# headers.net
KiCad netlist of a schematic drawn in Altium Designer
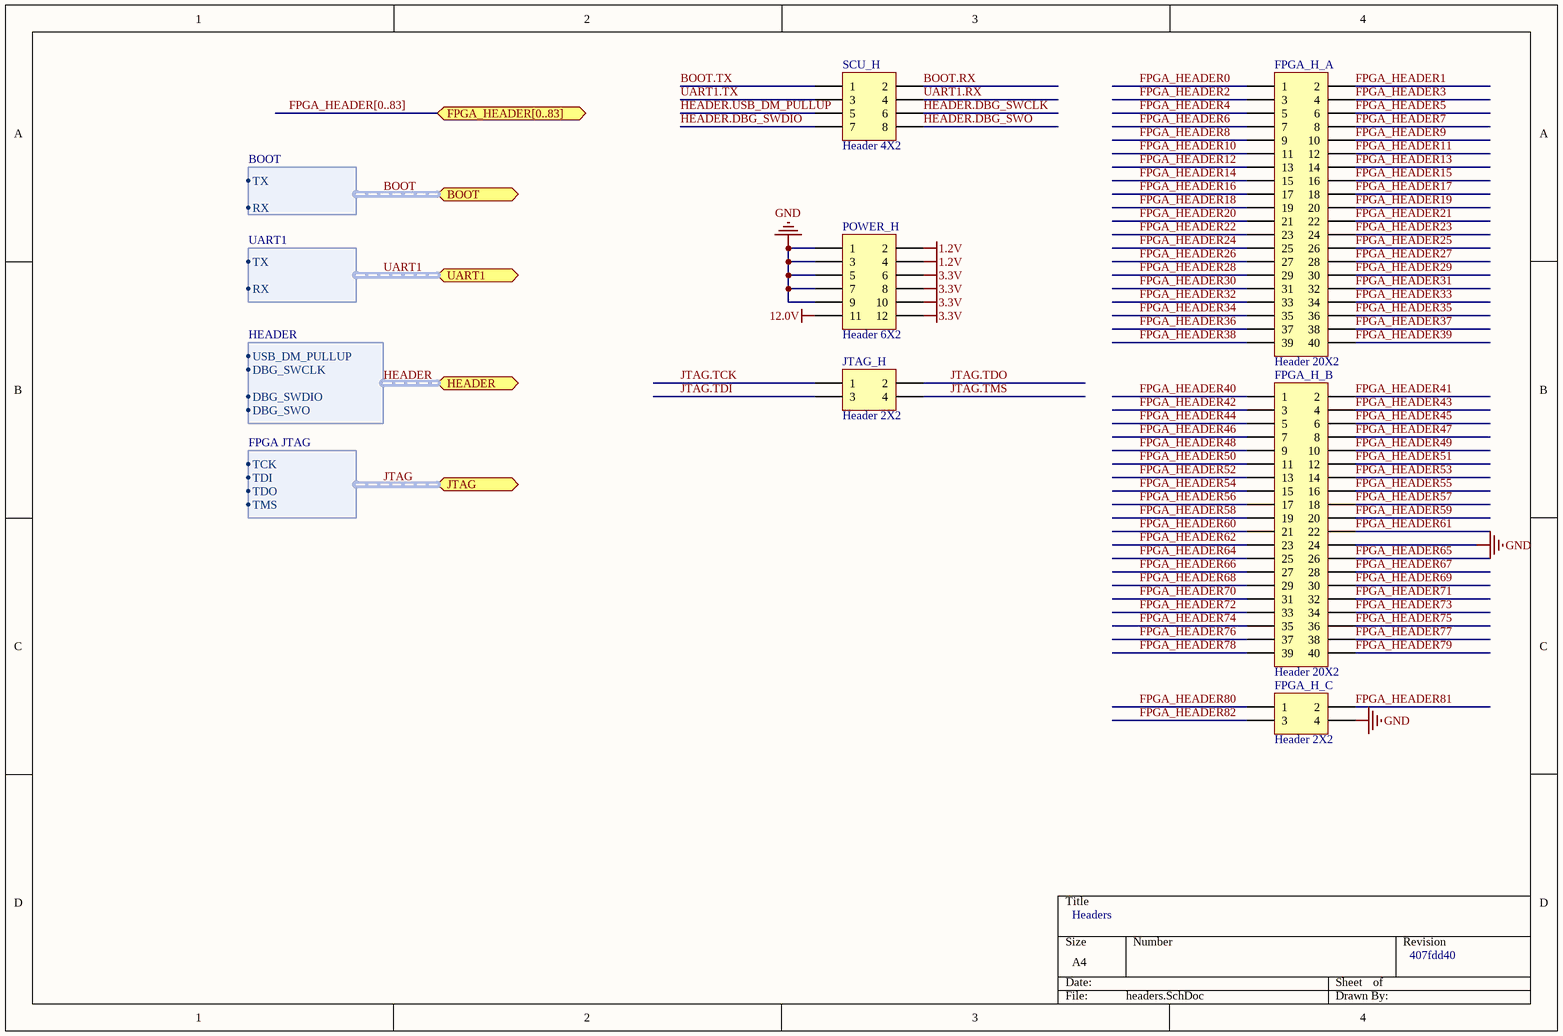
[diagram p0: headers.SchDoc]

(export (version "E")
  (design (tool "Eeschema 10.0.6"))
  (components
    (comp (ref "FPGA_H_A")
      (value "Header 20X2")
      (footprint "HDR2X20")
      (description "Header, 20-Pin, Dual row")
      (fields (field (name "PUBLISHER") "Altium Limited"))
      (libsource (lib "Miscellaneous Connectors") (part "Header 20X2"))
    )
    (comp (ref "FPGA_H_B")
      (value "Header 20X2")
      (footprint "HDR2X20")
      (description "Header, 20-Pin, Dual row")
      (fields (field (name "PUBLISHER") "Altium Limited"))
      (libsource (lib "Miscellaneous Connectors") (part "Header 20X2"))
    )
    (comp (ref "FPGA_H_C")
      (value "Header 2X2")
      (footprint "HDR2X2")
      (description "Header, 2-Pin, Dual row")
      (fields (field (name "PUBLISHER") "Altium Limited"))
      (libsource (lib "Miscellaneous Connectors") (part "Header 2X2"))
    )
    (comp (ref "JTAG_H")
      (value "Header 2X2")
      (footprint "HDR2X2")
      (description "Header, 2-Pin, Dual row")
      (fields (field (name "PUBLISHER") "Altium Limited"))
      (libsource (lib "Miscellaneous Connectors") (part "Header 2X2"))
    )
    (comp (ref "POWER_H")
      (value "Header 6X2")
      (footprint "HDR2X6")
      (description "Header, 6-Pin, Dual row")
      (fields (field (name "PUBLISHER") "Altium Limited"))
      (libsource (lib "Miscellaneous Connectors") (part "Header 6X2"))
    )
    (comp (ref "SCU_H")
      (value "Header 4X2")
      (footprint "HDR2X4")
      (description "Header, 4-Pin, Dual row")
      (fields (field (name "PUBLISHER") "Altium Limited"))
      (libsource (lib "Miscellaneous Connectors") (part "Header 4X2"))
    )
  )
  (nets
    (net (code "8") (name "/BOOT.RX") (class "Default")
      (node (ref "SCU_H") (pin "2") (pinfunction "2_2") (pintype "passive"))
    )
    (net (code "9") (name "/BOOT.TX") (class "Default")
      (node (ref "SCU_H") (pin "1") (pinfunction "1_1") (pintype "passive"))
    )
    (net (code "11") (name "/FPGA_HEADER0") (class "Default")
      (node (ref "FPGA_H_A") (pin "1") (pinfunction "1_1") (pintype "passive"))
    )
    (net (code "12") (name "/FPGA_HEADER1") (class "Default")
      (node (ref "FPGA_H_A") (pin "2") (pinfunction "2_2") (pintype "passive"))
    )
    (net (code "13") (name "/FPGA_HEADER2") (class "Default")
      (node (ref "FPGA_H_A") (pin "3") (pinfunction "3_3") (pintype "passive"))
    )
    (net (code "14") (name "/FPGA_HEADER3") (class "Default")
      (node (ref "FPGA_H_A") (pin "4") (pinfunction "4_4") (pintype "passive"))
    )
    (net (code "15") (name "/FPGA_HEADER4") (class "Default")
      (node (ref "FPGA_H_A") (pin "5") (pinfunction "5_5") (pintype "passive"))
    )
    (net (code "16") (name "/FPGA_HEADER5") (class "Default")
      (node (ref "FPGA_H_A") (pin "6") (pinfunction "6_6") (pintype "passive"))
    )
    (net (code "17") (name "/FPGA_HEADER6") (class "Default")
      (node (ref "FPGA_H_A") (pin "7") (pinfunction "7_7") (pintype "passive"))
    )
    (net (code "18") (name "/FPGA_HEADER7") (class "Default")
      (node (ref "FPGA_H_A") (pin "8") (pinfunction "8_8") (pintype "passive"))
    )
    (net (code "19") (name "/FPGA_HEADER8") (class "Default")
      (node (ref "FPGA_H_A") (pin "9") (pinfunction "9_9") (pintype "passive"))
    )
    (net (code "20") (name "/FPGA_HEADER9") (class "Default")
      (node (ref "FPGA_H_A") (pin "10") (pinfunction "10_10") (pintype "passive"))
    )
    (net (code "21") (name "/FPGA_HEADER10") (class "Default")
      (node (ref "FPGA_H_A") (pin "11") (pinfunction "11_11") (pintype "passive"))
    )
    (net (code "22") (name "/FPGA_HEADER11") (class "Default")
      (node (ref "FPGA_H_A") (pin "12") (pinfunction "12_12") (pintype "passive"))
    )
    (net (code "23") (name "/FPGA_HEADER12") (class "Default")
      (node (ref "FPGA_H_A") (pin "13") (pinfunction "13_13") (pintype "passive"))
    )
    (net (code "24") (name "/FPGA_HEADER13") (class "Default")
      (node (ref "FPGA_H_A") (pin "14") (pinfunction "14_14") (pintype "passive"))
    )
    (net (code "25") (name "/FPGA_HEADER14") (class "Default")
      (node (ref "FPGA_H_A") (pin "15") (pinfunction "15_15") (pintype "passive"))
    )
    (net (code "26") (name "/FPGA_HEADER15") (class "Default")
      (node (ref "FPGA_H_A") (pin "16") (pinfunction "16_16") (pintype "passive"))
    )
    (net (code "27") (name "/FPGA_HEADER16") (class "Default")
      (node (ref "FPGA_H_A") (pin "17") (pinfunction "17_17") (pintype "passive"))
    )
    (net (code "28") (name "/FPGA_HEADER17") (class "Default")
      (node (ref "FPGA_H_A") (pin "18") (pinfunction "18_18") (pintype "passive"))
    )
    (net (code "29") (name "/FPGA_HEADER18") (class "Default")
      (node (ref "FPGA_H_A") (pin "19") (pinfunction "19_19") (pintype "passive"))
    )
    (net (code "30") (name "/FPGA_HEADER19") (class "Default")
      (node (ref "FPGA_H_A") (pin "20") (pinfunction "20_20") (pintype "passive"))
    )
    (net (code "31") (name "/FPGA_HEADER20") (class "Default")
      (node (ref "FPGA_H_A") (pin "21") (pinfunction "21_21") (pintype "passive"))
    )
    (net (code "32") (name "/FPGA_HEADER21") (class "Default")
      (node (ref "FPGA_H_A") (pin "22") (pinfunction "22_22") (pintype "passive"))
    )
    (net (code "33") (name "/FPGA_HEADER22") (class "Default")
      (node (ref "FPGA_H_A") (pin "23") (pinfunction "23_23") (pintype "passive"))
    )
    (net (code "34") (name "/FPGA_HEADER23") (class "Default")
      (node (ref "FPGA_H_A") (pin "24") (pinfunction "24_24") (pintype "passive"))
    )
    (net (code "35") (name "/FPGA_HEADER24") (class "Default")
      (node (ref "FPGA_H_A") (pin "25") (pinfunction "25_25") (pintype "passive"))
    )
    (net (code "36") (name "/FPGA_HEADER25") (class "Default")
      (node (ref "FPGA_H_A") (pin "26") (pinfunction "26_26") (pintype "passive"))
    )
    (net (code "37") (name "/FPGA_HEADER26") (class "Default")
      (node (ref "FPGA_H_A") (pin "27") (pinfunction "27_27") (pintype "passive"))
    )
    (net (code "38") (name "/FPGA_HEADER27") (class "Default")
      (node (ref "FPGA_H_A") (pin "28") (pinfunction "28_28") (pintype "passive"))
    )
    (net (code "39") (name "/FPGA_HEADER28") (class "Default")
      (node (ref "FPGA_H_A") (pin "29") (pinfunction "29_29") (pintype "passive"))
    )
    (net (code "40") (name "/FPGA_HEADER29") (class "Default")
      (node (ref "FPGA_H_A") (pin "30") (pinfunction "30_30") (pintype "passive"))
    )
    (net (code "41") (name "/FPGA_HEADER30") (class "Default")
      (node (ref "FPGA_H_A") (pin "31") (pinfunction "31_31") (pintype "passive"))
    )
    (net (code "42") (name "/FPGA_HEADER31") (class "Default")
      (node (ref "FPGA_H_A") (pin "32") (pinfunction "32_32") (pintype "passive"))
    )
    (net (code "43") (name "/FPGA_HEADER32") (class "Default")
      (node (ref "FPGA_H_A") (pin "33") (pinfunction "33_33") (pintype "passive"))
    )
    (net (code "44") (name "/FPGA_HEADER33") (class "Default")
      (node (ref "FPGA_H_A") (pin "34") (pinfunction "34_34") (pintype "passive"))
    )
    (net (code "45") (name "/FPGA_HEADER34") (class "Default")
      (node (ref "FPGA_H_A") (pin "35") (pinfunction "35_35") (pintype "passive"))
    )
    (net (code "46") (name "/FPGA_HEADER35") (class "Default")
      (node (ref "FPGA_H_A") (pin "36") (pinfunction "36_36") (pintype "passive"))
    )
    (net (code "47") (name "/FPGA_HEADER36") (class "Default")
      (node (ref "FPGA_H_A") (pin "37") (pinfunction "37_37") (pintype "passive"))
    )
    (net (code "48") (name "/FPGA_HEADER37") (class "Default")
      (node (ref "FPGA_H_A") (pin "38") (pinfunction "38_38") (pintype "passive"))
    )
    (net (code "49") (name "/FPGA_HEADER38") (class "Default")
      (node (ref "FPGA_H_A") (pin "39") (pinfunction "39_39") (pintype "passive"))
    )
    (net (code "50") (name "/FPGA_HEADER39") (class "Default")
      (node (ref "FPGA_H_A") (pin "40") (pinfunction "40_40") (pintype "passive"))
    )
    (net (code "51") (name "/FPGA_HEADER40") (class "Default")
      (node (ref "FPGA_H_B") (pin "1") (pinfunction "1_1") (pintype "passive"))
    )
    (net (code "52") (name "/FPGA_HEADER41") (class "Default")
      (node (ref "FPGA_H_B") (pin "2") (pinfunction "2_2") (pintype "passive"))
    )
    (net (code "53") (name "/FPGA_HEADER42") (class "Default")
      (node (ref "FPGA_H_B") (pin "3") (pinfunction "3_3") (pintype "passive"))
    )
    (net (code "54") (name "/FPGA_HEADER43") (class "Default")
      (node (ref "FPGA_H_B") (pin "4") (pinfunction "4_4") (pintype "passive"))
    )
    (net (code "55") (name "/FPGA_HEADER44") (class "Default")
      (node (ref "FPGA_H_B") (pin "5") (pinfunction "5_5") (pintype "passive"))
    )
    (net (code "56") (name "/FPGA_HEADER45") (class "Default")
      (node (ref "FPGA_H_B") (pin "6") (pinfunction "6_6") (pintype "passive"))
    )
    (net (code "57") (name "/FPGA_HEADER46") (class "Default")
      (node (ref "FPGA_H_B") (pin "7") (pinfunction "7_7") (pintype "passive"))
    )
    (net (code "58") (name "/FPGA_HEADER47") (class "Default")
      (node (ref "FPGA_H_B") (pin "8") (pinfunction "8_8") (pintype "passive"))
    )
    (net (code "59") (name "/FPGA_HEADER48") (class "Default")
      (node (ref "FPGA_H_B") (pin "9") (pinfunction "9_9") (pintype "passive"))
    )
    (net (code "60") (name "/FPGA_HEADER49") (class "Default")
      (node (ref "FPGA_H_B") (pin "10") (pinfunction "10_10") (pintype "passive"))
    )
    (net (code "61") (name "/FPGA_HEADER50") (class "Default")
      (node (ref "FPGA_H_B") (pin "11") (pinfunction "11_11") (pintype "passive"))
    )
    (net (code "62") (name "/FPGA_HEADER51") (class "Default")
      (node (ref "FPGA_H_B") (pin "12") (pinfunction "12_12") (pintype "passive"))
    )
    (net (code "63") (name "/FPGA_HEADER52") (class "Default")
      (node (ref "FPGA_H_B") (pin "13") (pinfunction "13_13") (pintype "passive"))
    )
    (net (code "64") (name "/FPGA_HEADER53") (class "Default")
      (node (ref "FPGA_H_B") (pin "14") (pinfunction "14_14") (pintype "passive"))
    )
    (net (code "65") (name "/FPGA_HEADER54") (class "Default")
      (node (ref "FPGA_H_B") (pin "15") (pinfunction "15_15") (pintype "passive"))
    )
    (net (code "66") (name "/FPGA_HEADER55") (class "Default")
      (node (ref "FPGA_H_B") (pin "16") (pinfunction "16_16") (pintype "passive"))
    )
    (net (code "67") (name "/FPGA_HEADER56") (class "Default")
      (node (ref "FPGA_H_B") (pin "17") (pinfunction "17_17") (pintype "passive"))
    )
    (net (code "68") (name "/FPGA_HEADER57") (class "Default")
      (node (ref "FPGA_H_B") (pin "18") (pinfunction "18_18") (pintype "passive"))
    )
    (net (code "69") (name "/FPGA_HEADER58") (class "Default")
      (node (ref "FPGA_H_B") (pin "19") (pinfunction "19_19") (pintype "passive"))
    )
    (net (code "70") (name "/FPGA_HEADER59") (class "Default")
      (node (ref "FPGA_H_B") (pin "20") (pinfunction "20_20") (pintype "passive"))
    )
    (net (code "71") (name "/FPGA_HEADER60") (class "Default")
      (node (ref "FPGA_H_B") (pin "21") (pinfunction "21_21") (pintype "passive"))
    )
    (net (code "72") (name "/FPGA_HEADER61") (class "Default")
      (node (ref "FPGA_H_B") (pin "22") (pinfunction "22_22") (pintype "passive"))
    )
    (net (code "73") (name "/FPGA_HEADER62") (class "Default")
      (node (ref "FPGA_H_B") (pin "23") (pinfunction "23_23") (pintype "passive"))
    )
    (net (code "74") (name "/FPGA_HEADER64") (class "Default")
      (node (ref "FPGA_H_B") (pin "25") (pinfunction "25_25") (pintype "passive"))
    )
    (net (code "75") (name "/FPGA_HEADER65") (class "Default")
      (node (ref "FPGA_H_B") (pin "26") (pinfunction "26_26") (pintype "passive"))
    )
    (net (code "76") (name "/FPGA_HEADER66") (class "Default")
      (node (ref "FPGA_H_B") (pin "27") (pinfunction "27_27") (pintype "passive"))
    )
    (net (code "77") (name "/FPGA_HEADER67") (class "Default")
      (node (ref "FPGA_H_B") (pin "28") (pinfunction "28_28") (pintype "passive"))
    )
    (net (code "78") (name "/FPGA_HEADER68") (class "Default")
      (node (ref "FPGA_H_B") (pin "29") (pinfunction "29_29") (pintype "passive"))
    )
    (net (code "79") (name "/FPGA_HEADER69") (class "Default")
      (node (ref "FPGA_H_B") (pin "30") (pinfunction "30_30") (pintype "passive"))
    )
    (net (code "80") (name "/FPGA_HEADER70") (class "Default")
      (node (ref "FPGA_H_B") (pin "31") (pinfunction "31_31") (pintype "passive"))
    )
    (net (code "81") (name "/FPGA_HEADER71") (class "Default")
      (node (ref "FPGA_H_B") (pin "32") (pinfunction "32_32") (pintype "passive"))
    )
    (net (code "82") (name "/FPGA_HEADER72") (class "Default")
      (node (ref "FPGA_H_B") (pin "33") (pinfunction "33_33") (pintype "passive"))
    )
    (net (code "83") (name "/FPGA_HEADER73") (class "Default")
      (node (ref "FPGA_H_B") (pin "34") (pinfunction "34_34") (pintype "passive"))
    )
    (net (code "84") (name "/FPGA_HEADER74") (class "Default")
      (node (ref "FPGA_H_B") (pin "35") (pinfunction "35_35") (pintype "passive"))
    )
    (net (code "85") (name "/FPGA_HEADER75") (class "Default")
      (node (ref "FPGA_H_B") (pin "36") (pinfunction "36_36") (pintype "passive"))
    )
    (net (code "86") (name "/FPGA_HEADER76") (class "Default")
      (node (ref "FPGA_H_B") (pin "37") (pinfunction "37_37") (pintype "passive"))
    )
    (net (code "87") (name "/FPGA_HEADER77") (class "Default")
      (node (ref "FPGA_H_B") (pin "38") (pinfunction "38_38") (pintype "passive"))
    )
    (net (code "88") (name "/FPGA_HEADER78") (class "Default")
      (node (ref "FPGA_H_B") (pin "39") (pinfunction "39_39") (pintype "passive"))
    )
    (net (code "89") (name "/FPGA_HEADER79") (class "Default")
      (node (ref "FPGA_H_B") (pin "40") (pinfunction "40_40") (pintype "passive"))
    )
    (net (code "90") (name "/FPGA_HEADER80") (class "Default")
      (node (ref "FPGA_H_C") (pin "1") (pinfunction "1_1") (pintype "passive"))
    )
    (net (code "91") (name "/FPGA_HEADER81") (class "Default")
      (node (ref "FPGA_H_C") (pin "2") (pinfunction "2_2") (pintype "passive"))
    )
    (net (code "92") (name "/FPGA_HEADER82") (class "Default")
      (node (ref "FPGA_H_C") (pin "3") (pinfunction "3_3") (pintype "passive"))
    )
    (net (code "94") (name "/HEADER.DBG_SWCLK") (class "Default")
      (node (ref "SCU_H") (pin "6") (pinfunction "6_6") (pintype "passive"))
    )
    (net (code "95") (name "/HEADER.DBG_SWDIO") (class "Default")
      (node (ref "SCU_H") (pin "7") (pinfunction "7_7") (pintype "passive"))
    )
    (net (code "96") (name "/HEADER.DBG_SWO") (class "Default")
      (node (ref "SCU_H") (pin "8") (pinfunction "8_8") (pintype "passive"))
    )
    (net (code "97") (name "/HEADER.USB_DM_PULLUP") (class "Default")
      (node (ref "SCU_H") (pin "5") (pinfunction "5_5") (pintype "passive"))
    )
    (net (code "99") (name "/JTAG.TCK") (class "Default")
      (node (ref "JTAG_H") (pin "1") (pinfunction "1_1") (pintype "passive"))
    )
    (net (code "100") (name "/JTAG.TDI") (class "Default")
      (node (ref "JTAG_H") (pin "3") (pinfunction "3_3") (pintype "passive"))
    )
    (net (code "101") (name "/JTAG.TDO") (class "Default")
      (node (ref "JTAG_H") (pin "2") (pinfunction "2_2") (pintype "passive"))
    )
    (net (code "102") (name "/JTAG.TMS") (class "Default")
      (node (ref "JTAG_H") (pin "4") (pinfunction "4_4") (pintype "passive"))
    )
    (net (code "104") (name "/UART1.RX") (class "Default")
      (node (ref "SCU_H") (pin "4") (pinfunction "4_4") (pintype "passive"))
    )
    (net (code "105") (name "/UART1.TX") (class "Default")
      (node (ref "SCU_H") (pin "3") (pinfunction "3_3") (pintype "passive"))
    )
    (net (code "107") (name "1.2V") (class "Default")
      (node (ref "POWER_H") (pin "2") (pinfunction "2_2") (pintype "passive"))
      (node (ref "POWER_H") (pin "4") (pinfunction "4_4") (pintype "passive"))
    )
    (net (code "108") (name "3.3V") (class "Default")
      (node (ref "POWER_H") (pin "10") (pinfunction "10_10") (pintype "passive"))
      (node (ref "POWER_H") (pin "12") (pinfunction "12_12") (pintype "passive"))
      (node (ref "POWER_H") (pin "6") (pinfunction "6_6") (pintype "passive"))
      (node (ref "POWER_H") (pin "8") (pinfunction "8_8") (pintype "passive"))
    )
    (net (code "109") (name "12.0V") (class "Default")
      (node (ref "POWER_H") (pin "11") (pinfunction "11_11") (pintype "passive"))
    )
    (net (code "110") (name "GND") (class "Default")
      (node (ref "FPGA_H_B") (pin "24") (pinfunction "24_24") (pintype "passive"))
      (node (ref "FPGA_H_C") (pin "4") (pinfunction "4_4") (pintype "passive"))
      (node (ref "POWER_H") (pin "1") (pinfunction "1_1") (pintype "passive"))
      (node (ref "POWER_H") (pin "3") (pinfunction "3_3") (pintype "passive"))
      (node (ref "POWER_H") (pin "5") (pinfunction "5_5") (pintype "passive"))
      (node (ref "POWER_H") (pin "7") (pinfunction "7_7") (pintype "passive"))
      (node (ref "POWER_H") (pin "9") (pinfunction "9_9") (pintype "passive"))
    )
  )
)
